# arduino_uno_mod.net
KiCad netlist of a schematic drawn in EAGLE
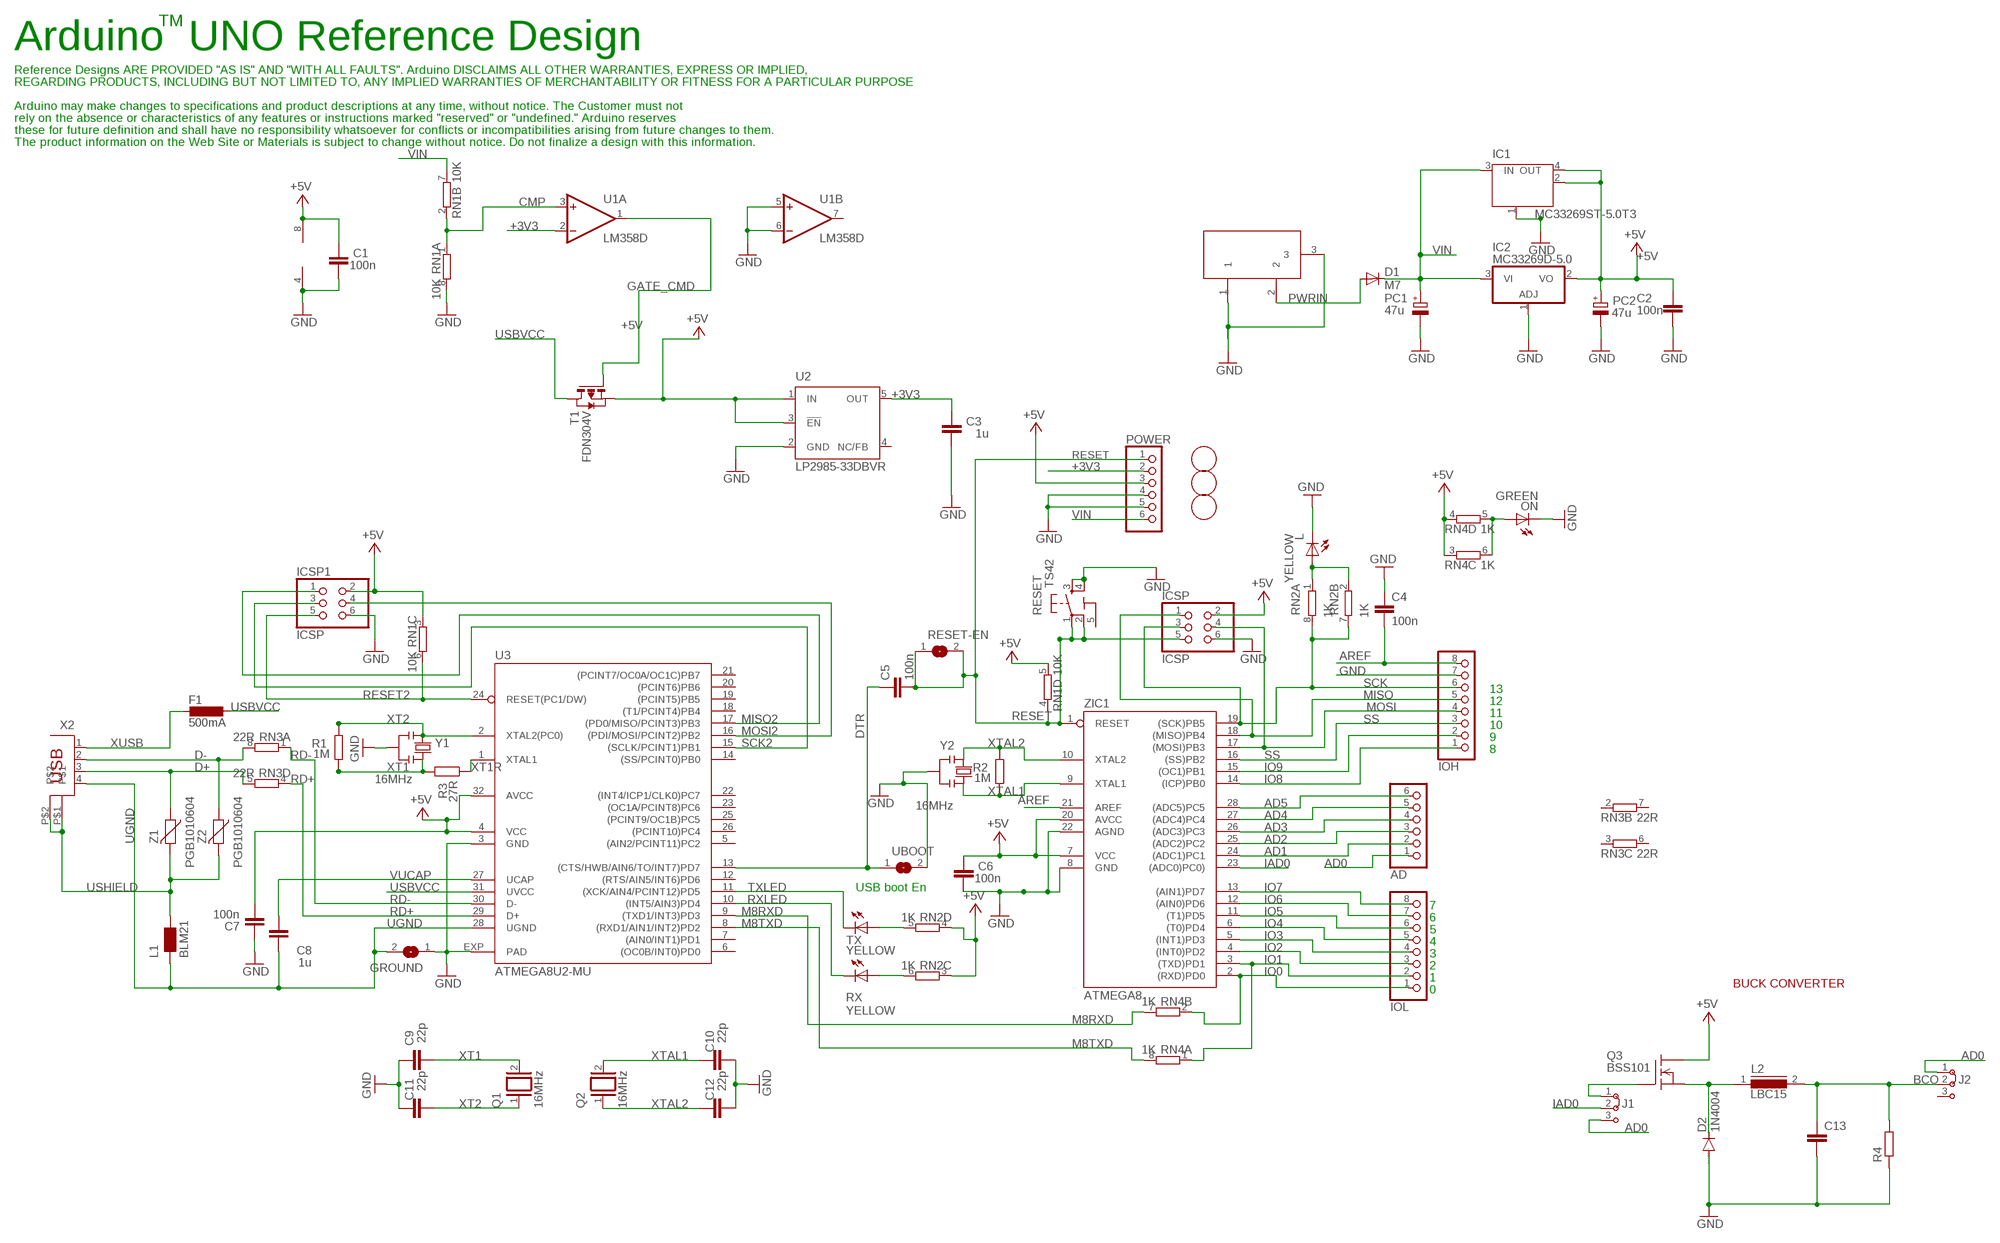
[diagram p0: schematic, sheet 1]

(export (version "E")
  (design (tool "Eeschema 10.0.6"))
  (components
    (comp (ref "AD")
      (value "PINHD-1X6")
      (footprint "eagle-import:1X06")
      (libsource (lib "eagle-import") (part "PINHD-1X6"))
    )
    (comp (ref "C1")
      (value "100n")
      (footprint "eagle-import:C0603-ROUND")
      (libsource (lib "eagle-import") (part "C-EU0603-RND"))
    )
    (comp (ref "C2")
      (value "100n")
      (footprint "eagle-import:C0603-ROUND")
      (libsource (lib "eagle-import") (part "C-EU0603-RND"))
    )
    (comp (ref "C3")
      (value "1u")
      (footprint "eagle-import:C0603-ROUND")
      (libsource (lib "eagle-import") (part "C-EU0603-RND"))
    )
    (comp (ref "C4")
      (value "100n")
      (footprint "eagle-import:C0603-ROUND")
      (libsource (lib "eagle-import") (part "C-EU0603-RND"))
    )
    (comp (ref "C5")
      (value "100n")
      (footprint "eagle-import:C0603-ROUND")
      (libsource (lib "eagle-import") (part "C-EU0603-RND"))
    )
    (comp (ref "C6")
      (value "100n")
      (footprint "eagle-import:C0603-ROUND")
      (libsource (lib "eagle-import") (part "C-EU0603-RND"))
    )
    (comp (ref "C7")
      (value "100n")
      (footprint "eagle-import:C0603-ROUND")
      (libsource (lib "eagle-import") (part "C-EU0603-RND"))
    )
    (comp (ref "C8")
      (value "1u")
      (footprint "eagle-import:C0603-ROUND")
      (libsource (lib "eagle-import") (part "C-EU0603-RND"))
    )
    (comp (ref "C9")
      (value "22p")
      (footprint "eagle-import:C0603-ROUND")
      (libsource (lib "eagle-import") (part "C-EU0603-RND"))
    )
    (comp (ref "C10")
      (value "22p")
      (footprint "eagle-import:C0603-ROUND")
      (libsource (lib "eagle-import") (part "C-EU0603-RND"))
    )
    (comp (ref "C11")
      (value "22p")
      (footprint "eagle-import:C0603-ROUND")
      (libsource (lib "eagle-import") (part "C-EU0603-RND"))
    )
    (comp (ref "C12")
      (value "22p")
      (footprint "eagle-import:C0603-ROUND")
      (libsource (lib "eagle-import") (part "C-EU0603-RND"))
    )
    (comp (ref "C13")
      (value "C2.5/2")
      (footprint "eagle-import:C2.5-2")
      (libsource (lib "eagle-import") (part "C2.5/2"))
    )
    (comp (ref "D1")
      (value "M7")
      (footprint "eagle-import:SMB")
      (libsource (lib "eagle-import") (part "DIODE-SMB"))
    )
    (comp (ref "D2")
      (value "1N4004")
      (footprint "eagle-import:DO41-10")
      (libsource (lib "eagle-import") (part "1N4004"))
    )
    (comp (ref "F1")
      (value "500mA")
      (footprint "eagle-import:L1812")
      (libsource (lib "eagle-import") (part "L-EUL1812"))
    )
    (comp (ref "GROUND")
      (value "SJ")
      (footprint "eagle-import:SJ")
      (libsource (lib "eagle-import") (part "SJ"))
    )
    (comp (ref "IC1")
      (value "MC33269ST-5.0T3")
      (footprint "eagle-import:SOT223")
      (libsource (lib "eagle-import") (part "MC33269ST-3.3T3"))
    )
    (comp (ref "IC2")
      (value "MC33269D-5.0")
      (footprint "eagle-import:DPACK")
      (libsource (lib "eagle-import") (part "MC33269?D-5.0"))
    )
    (comp (ref "ICSP")
      (value "ICSP")
      (footprint "eagle-import:2X03")
      (libsource (lib "eagle-import") (part "PINHD-2X3"))
    )
    (comp (ref "ICSP1")
      (value "ICSP")
      (footprint "eagle-import:2X03")
      (libsource (lib "eagle-import") (part "PINHD-2X3"))
    )
    (comp (ref "IOH")
      (value "PINHD-1X8")
      (footprint "eagle-import:1X08")
      (libsource (lib "eagle-import") (part "PINHD-1X8"))
    )
    (comp (ref "IOL")
      (value "PINHD-1X8")
      (footprint "eagle-import:1X08")
      (libsource (lib "eagle-import") (part "PINHD-1X8"))
    )
    (comp (ref "J1")
      (value "J2X2MM")
      (footprint "eagle-import:04C")
      (libsource (lib "eagle-import") (part "J2X2MM"))
    )
    (comp (ref "J2")
      (value "J2X2MM")
      (footprint "eagle-import:04C")
      (libsource (lib "eagle-import") (part "J2X2MM"))
    )
    (comp (ref "L")
      (value "YELLOW")
      (footprint "eagle-import:CHIP-LED0805")
      (libsource (lib "eagle-import") (part "LEDCHIP-LED0805"))
    )
    (comp (ref "L1")
      (value "BLM21")
      (footprint "eagle-import:0805")
      (libsource (lib "eagle-import") (part "WE-CBF_0805"))
    )
    (comp (ref "L2")
      (value "LBC15")
      (footprint "eagle-import:LBC15")
      (libsource (lib "eagle-import") (part "LBC15"))
    )
    (comp (ref "ON")
      (value "GREEN")
      (footprint "eagle-import:CHIP-LED0805")
      (libsource (lib "eagle-import") (part "LEDCHIP-LED0805"))
    )
    (comp (ref "PC1")
      (value "47u")
      (footprint "eagle-import:PANASONIC_D")
      (libsource (lib "eagle-import") (part "CPOL-EUD"))
    )
    (comp (ref "PC2")
      (value "47u")
      (footprint "eagle-import:PANASONIC_D")
      (libsource (lib "eagle-import") (part "CPOL-EUD"))
    )
    (comp (ref "POWER")
      (value "PINHD-1X6")
      (footprint "eagle-import:1X06")
      (libsource (lib "eagle-import") (part "PINHD-1X6"))
    )
    (comp (ref "Q1")
      (value "16MHz")
      (footprint "eagle-import:QS")
      (libsource (lib "eagle-import") (part "XTAL/S"))
    )
    (comp (ref "Q2")
      (value "16MHz")
      (footprint "eagle-import:QS")
      (libsource (lib "eagle-import") (part "XTAL/S"))
    )
    (comp (ref "Q3")
      (value "BSS101")
      (footprint "eagle-import:TO92")
      (libsource (lib "eagle-import") (part "BSS101"))
    )
    (comp (ref "R1")
      (value "1M")
      (footprint "eagle-import:R0603-ROUND")
      (libsource (lib "eagle-import") (part "R-EU_R0603"))
    )
    (comp (ref "R2")
      (value "1M")
      (footprint "eagle-import:R0603-ROUND")
      (libsource (lib "eagle-import") (part "R-EU_R0603"))
    )
    (comp (ref "R3")
      (value "27R")
      (footprint "eagle-import:R0603-ROUND")
      (libsource (lib "eagle-import") (part "R-EU_R0603"))
    )
    (comp (ref "R4")
      (value "R-EU_0207/10")
      (footprint "eagle-import:0207_10")
      (libsource (lib "eagle-import") (part "rcl_334_R-EU_0207/10"))
    )
    (comp (ref "RESET")
      (value "TS42")
      (footprint "eagle-import:TS42")
      (libsource (lib "eagle-import") (part "TS42"))
    )
    (comp (ref "RESET-EN")
      (value "SJ")
      (footprint "eagle-import:SJ")
      (libsource (lib "eagle-import") (part "SJ"))
    )
    (comp (ref "RN1")
      (value "10K")
      (footprint "eagle-import:CAY16")
      (libsource (lib "eagle-import") (part "4R-NCAY16"))
    )
    (comp (ref "RN2")
      (value "1K")
      (footprint "eagle-import:CAY16")
      (libsource (lib "eagle-import") (part "4R-NCAY16"))
    )
    (comp (ref "RN3")
      (value "22R")
      (footprint "eagle-import:CAY16")
      (libsource (lib "eagle-import") (part "4R-NCAY16"))
    )
    (comp (ref "RN4")
      (value "1K")
      (footprint "eagle-import:CAY16")
      (libsource (lib "eagle-import") (part "4R-NCAY16"))
    )
    (comp (ref "RX")
      (value "YELLOW")
      (footprint "eagle-import:CHIP-LED0805")
      (libsource (lib "eagle-import") (part "LEDCHIP-LED0805"))
    )
    (comp (ref "T1")
      (value "FDN304V")
      (footprint "eagle-import:SOT-23")
      (libsource (lib "eagle-import") (part "PMOSSOT23"))
    )
    (comp (ref "TX")
      (value "YELLOW")
      (footprint "eagle-import:CHIP-LED0805")
      (libsource (lib "eagle-import") (part "LEDCHIP-LED0805"))
    )
    (comp (ref "U$3")
      (value "FIDUCIALMOUNT")
      (footprint "eagle-import:FIDUCIA-MOUNT")
      (libsource (lib "eagle-import") (part "FIDUCIALMOUNT"))
    )
    (comp (ref "U$4")
      (value "FIDUCIALMOUNT")
      (footprint "eagle-import:FIDUCIA-MOUNT")
      (libsource (lib "eagle-import") (part "FIDUCIALMOUNT"))
    )
    (comp (ref "U$6")
      (value "FIDUCIALMOUNT")
      (footprint "eagle-import:FIDUCIA-MOUNT")
      (libsource (lib "eagle-import") (part "FIDUCIALMOUNT"))
    )
    (comp (ref "U1")
      (value "LM358D")
      (footprint "eagle-import:SO08")
      (libsource (lib "eagle-import") (part "LM358D"))
    )
    (comp (ref "U2")
      (value "LP2985-33DBVR")
      (footprint "eagle-import:SOT23-DBV")
      (libsource (lib "eagle-import") (part "TPS77033"))
    )
    (comp (ref "U3")
      (value "ATMEGA8U2-MU")
      (footprint "eagle-import:QFN32")
      (libsource (lib "eagle-import") (part "ATMEGA8U2-MU"))
    )
    (comp (ref "UBOOT")
      (value "SJ")
      (footprint "eagle-import:SJ")
      (libsource (lib "eagle-import") (part "SJ"))
    )
    (comp (ref "X1")
      (value "DC21MMX")
      (footprint "eagle-import:DC-21MM")
      (libsource (lib "eagle-import") (part "DC21MMX"))
    )
    (comp (ref "X2")
      (value "PN61729")
      (footprint "eagle-import:PN61729")
      (libsource (lib "eagle-import") (part "PN61729"))
    )
    (comp (ref "Y1")
      (value "16MHz")
      (footprint "eagle-import:RESONATOR")
      (libsource (lib "eagle-import") (part "RESONATORMU"))
    )
    (comp (ref "Y2")
      (value "16MHz")
      (footprint "eagle-import:RESONATOR")
      (libsource (lib "eagle-import") (part "RESONATORMU"))
    )
    (comp (ref "Z1")
      (value "PGB1010604")
      (footprint "eagle-import:CT_CN0603")
      (libsource (lib "eagle-import") (part "VARISTORCN0603"))
    )
    (comp (ref "Z2")
      (value "PGB1010604")
      (footprint "eagle-import:CT_CN0603")
      (libsource (lib "eagle-import") (part "VARISTORCN0603"))
    )
    (comp (ref "ZIC1")
      (value "ATMEGA8")
      (footprint "eagle-import:DIL28-3")
      (libsource (lib "eagle-import") (part "AT90S4433P"))
    )
  )
  (nets
    (net (code "1") (name "+5V") (class "Default")
      (node (ref "C1") (pin "2") (pinfunction "2_2") (pintype "passive"))
      (node (ref "C2") (pin "2") (pinfunction "2_2") (pintype "passive"))
      (node (ref "C6") (pin "2") (pinfunction "2_2") (pintype "passive"))
      (node (ref "C7") (pin "1") (pinfunction "1_1") (pintype "passive"))
      (node (ref "IC1") (pin "2") (pinfunction "OUT_2") (pintype "passive"))
      (node (ref "IC1") (pin "4") (pinfunction "OUT_4") (pintype "passive"))
      (node (ref "IC2") (pin "2") (pinfunction "VO_2") (pintype "passive"))
      (node (ref "ICSP") (pin "2") (pinfunction "2_2") (pintype "passive"))
      (node (ref "ICSP1") (pin "2") (pinfunction "2_2") (pintype "passive"))
      (node (ref "PC2") (pin "+") (pinfunction "+_+") (pintype "passive"))
      (node (ref "POWER") (pin "3") (pinfunction "3_3") (pintype "passive"))
      (node (ref "Q3") (pin "3") (pinfunction "D_3") (pintype "passive"))
      (node (ref "RN1") (pin "3") (pinfunction "1_3") (pintype "passive"))
      (node (ref "RN1") (pin "5") (pinfunction "2_5") (pintype "passive"))
      (node (ref "RN2") (pin "3") (pinfunction "1_3") (pintype "passive"))
      (node (ref "RN2") (pin "4") (pinfunction "1_4") (pintype "passive"))
      (node (ref "RN4") (pin "3") (pinfunction "1_3") (pintype "passive"))
      (node (ref "RN4") (pin "4") (pinfunction "1_4") (pintype "passive"))
      (node (ref "T1") (pin "2") (pinfunction "S_2") (pintype "passive"))
      (node (ref "U1") (pin "8") (pinfunction "V+_8") (pintype "power_in"))
      (node (ref "U2") (pin "1") (pinfunction "IN_1") (pintype "input"))
      (node (ref "U2") (pin "3") (pinfunction "~{EN}_3") (pintype "input"))
      (node (ref "U3") (pin "32") (pinfunction "AVCC_32") (pintype "power_in"))
      (node (ref "U3") (pin "4") (pinfunction "VCC_4") (pintype "power_in"))
      (node (ref "ZIC1") (pin "20") (pinfunction "AVCC_20") (pintype "power_in"))
      (node (ref "ZIC1") (pin "7") (pinfunction "VCC_7") (pintype "power_in"))
    )
    (net (code "2") (name "/+3V3") (class "Default")
      (node (ref "C3") (pin "2") (pinfunction "2_2") (pintype "passive"))
      (node (ref "POWER") (pin "2") (pinfunction "2_2") (pintype "passive"))
      (node (ref "U1") (pin "2") (pinfunction "-IN_2") (pintype "input"))
      (node (ref "U2") (pin "5") (pinfunction "OUT_5") (pintype "passive"))
    )
    (net (code "3") (name "/5-GND") (class "Default")
      (node (ref "RESET") (pin "5") (pinfunction "5-GND_5") (pintype "power_in"))
    )
    (net (code "4") (name "/AD0") (class "Default")
      (node (ref "AD") (pin "1") (pinfunction "1_1") (pintype "passive"))
      (node (ref "J1") (pin "3") (pinfunction "3_3") (pintype "passive"))
      (node (ref "J2") (pin "1") (pinfunction "1_1") (pintype "passive"))
    )
    (net (code "5") (name "/AD1") (class "Default")
      (node (ref "AD") (pin "2") (pinfunction "2_2") (pintype "passive"))
      (node (ref "ZIC1") (pin "24") (pinfunction "(ADC1)PC1_24") (pintype "bidirectional"))
    )
    (net (code "6") (name "/AD2") (class "Default")
      (node (ref "AD") (pin "3") (pinfunction "3_3") (pintype "passive"))
      (node (ref "ZIC1") (pin "25") (pinfunction "(ADC2)PC2_25") (pintype "bidirectional"))
    )
    (net (code "7") (name "/AD3") (class "Default")
      (node (ref "AD") (pin "4") (pinfunction "4_4") (pintype "passive"))
      (node (ref "ZIC1") (pin "26") (pinfunction "(ADC3)PC3_26") (pintype "bidirectional"))
    )
    (net (code "8") (name "/AD4") (class "Default")
      (node (ref "AD") (pin "5") (pinfunction "5_5") (pintype "passive"))
      (node (ref "ZIC1") (pin "27") (pinfunction "(ADC4)PC4_27") (pintype "bidirectional"))
    )
    (net (code "9") (name "/AD5") (class "Default")
      (node (ref "AD") (pin "6") (pinfunction "6_6") (pintype "passive"))
      (node (ref "ZIC1") (pin "28") (pinfunction "(ADC5)PC5_28") (pintype "bidirectional"))
    )
    (net (code "10") (name "/AREF") (class "Default")
      (node (ref "C4") (pin "2") (pinfunction "2_2") (pintype "passive"))
      (node (ref "IOH") (pin "8") (pinfunction "8_8") (pintype "passive"))
      (node (ref "ZIC1") (pin "21") (pinfunction "AREF_21") (pintype "passive"))
    )
    (net (code "11") (name "/BCO") (class "Default")
      (node (ref "C13") (pin "1") (pinfunction "1_1") (pintype "passive"))
      (node (ref "J2") (pin "2") (pinfunction "2_2") (pintype "passive"))
      (node (ref "L2") (pin "2") (pinfunction "2_2") (pintype "passive"))
      (node (ref "R4") (pin "2") (pinfunction "2_2") (pintype "passive"))
    )
    (net (code "12") (name "/CMP") (class "Default")
      (node (ref "RN1") (pin "1") (pinfunction "1_1") (pintype "passive"))
      (node (ref "RN1") (pin "2") (pinfunction "1_2") (pintype "passive"))
      (node (ref "U1") (pin "3") (pinfunction "+IN_3") (pintype "input"))
    )
    (net (code "13") (name "/D+") (class "Default")
      (node (ref "RN3") (pin "5") (pinfunction "2_5") (pintype "passive"))
      (node (ref "X2") (pin "3") (pinfunction "3_3") (pintype "bidirectional"))
      (node (ref "Z1") (pin "1") (pinfunction "1_1") (pintype "passive"))
    )
    (net (code "14") (name "/D-") (class "Default")
      (node (ref "RN3") (pin "8") (pinfunction "2_8") (pintype "passive"))
      (node (ref "X2") (pin "2") (pinfunction "2_2") (pintype "bidirectional"))
      (node (ref "Z2") (pin "1") (pinfunction "1_1") (pintype "passive"))
    )
    (net (code "15") (name "/DTR") (class "Default")
      (node (ref "C5") (pin "1") (pinfunction "1_1") (pintype "passive"))
      (node (ref "U3") (pin "13") (pinfunction "(CTS/HWB/AIN6/TO/INT7)PD7_13") (pintype "bidirectional"))
      (node (ref "UBOOT") (pin "1") (pinfunction "1_1") (pintype "passive"))
    )
    (net (code "16") (name "/GATE_CMD") (class "Default")
      (node (ref "T1") (pin "3") (pinfunction "G_3") (pintype "passive"))
      (node (ref "U1") (pin "1") (pinfunction "OUT_1") (pintype "output"))
    )
    (net (code "17") (name "/IAD0") (class "Default")
      (node (ref "J1") (pin "2") (pinfunction "2_2") (pintype "passive"))
      (node (ref "ZIC1") (pin "23") (pinfunction "(ADC0)PC0)_23") (pintype "bidirectional"))
    )
    (net (code "18") (name "/IO0") (class "Default")
      (node (ref "IOL") (pin "1") (pinfunction "1_1") (pintype "passive"))
      (node (ref "RN4") (pin "2") (pinfunction "1_2") (pintype "passive"))
      (node (ref "ZIC1") (pin "2") (pinfunction "(RXD)PD0_2") (pintype "bidirectional"))
    )
    (net (code "19") (name "/IO1") (class "Default")
      (node (ref "IOL") (pin "2") (pinfunction "2_2") (pintype "passive"))
      (node (ref "RN4") (pin "1") (pinfunction "1_1") (pintype "passive"))
      (node (ref "ZIC1") (pin "3") (pinfunction "(TXD)PD1_3") (pintype "bidirectional"))
    )
    (net (code "20") (name "/IO2") (class "Default")
      (node (ref "IOL") (pin "3") (pinfunction "3_3") (pintype "passive"))
      (node (ref "ZIC1") (pin "4") (pinfunction "(INT0)PD2_4") (pintype "bidirectional"))
    )
    (net (code "21") (name "/IO3") (class "Default")
      (node (ref "IOL") (pin "4") (pinfunction "4_4") (pintype "passive"))
      (node (ref "ZIC1") (pin "5") (pinfunction "(INT1)PD3_5") (pintype "bidirectional"))
    )
    (net (code "22") (name "/IO4") (class "Default")
      (node (ref "IOL") (pin "5") (pinfunction "5_5") (pintype "passive"))
      (node (ref "ZIC1") (pin "6") (pinfunction "(T0)PD4_6") (pintype "bidirectional"))
    )
    (net (code "23") (name "/IO5") (class "Default")
      (node (ref "IOL") (pin "6") (pinfunction "6_6") (pintype "passive"))
      (node (ref "ZIC1") (pin "11") (pinfunction "(T1)PD5_11") (pintype "bidirectional"))
    )
    (net (code "24") (name "/IO6") (class "Default")
      (node (ref "IOL") (pin "7") (pinfunction "7_7") (pintype "passive"))
      (node (ref "ZIC1") (pin "12") (pinfunction "(AIN0)PD6_12") (pintype "bidirectional"))
    )
    (net (code "25") (name "/IO7") (class "Default")
      (node (ref "IOL") (pin "8") (pinfunction "8_8") (pintype "passive"))
      (node (ref "ZIC1") (pin "13") (pinfunction "(AIN1)PD7_13") (pintype "bidirectional"))
    )
    (net (code "26") (name "/IO8") (class "Default")
      (node (ref "IOH") (pin "1") (pinfunction "1_1") (pintype "passive"))
      (node (ref "ZIC1") (pin "14") (pinfunction "(ICP)PB0_14") (pintype "bidirectional"))
    )
    (net (code "27") (name "/IO9") (class "Default")
      (node (ref "IOH") (pin "2") (pinfunction "2_2") (pintype "passive"))
      (node (ref "ZIC1") (pin "15") (pinfunction "(OC1)PB1_15") (pintype "bidirectional"))
    )
    (net (code "28") (name "/M8RXD") (class "Default")
      (node (ref "RN4") (pin "7") (pinfunction "2_7") (pintype "passive"))
      (node (ref "U3") (pin "9") (pinfunction "(TXD1/INT3)PD3_9") (pintype "bidirectional"))
    )
    (net (code "29") (name "/M8TXD") (class "Default")
      (node (ref "RN4") (pin "8") (pinfunction "2_8") (pintype "passive"))
      (node (ref "U3") (pin "8") (pinfunction "(RXD1/AIN1/INT2)PD2_8") (pintype "bidirectional"))
    )
    (net (code "30") (name "/MISO") (class "Default")
      (node (ref "ICSP") (pin "1") (pinfunction "1_1") (pintype "passive"))
      (node (ref "IOH") (pin "5") (pinfunction "5_5") (pintype "passive"))
      (node (ref "ZIC1") (pin "18") (pinfunction "(MISO)PB4_18") (pintype "bidirectional"))
    )
    (net (code "31") (name "/MISO2") (class "Default")
      (node (ref "ICSP1") (pin "1") (pinfunction "1_1") (pintype "passive"))
      (node (ref "U3") (pin "17") (pinfunction "(PD0/MISO/PCINT3)PB3_17") (pintype "bidirectional"))
    )
    (net (code "32") (name "/MOSI") (class "Default")
      (node (ref "ICSP") (pin "4") (pinfunction "4_4") (pintype "passive"))
      (node (ref "IOH") (pin "4") (pinfunction "4_4") (pintype "passive"))
      (node (ref "ZIC1") (pin "17") (pinfunction "(MOSI)PB3_17") (pintype "bidirectional"))
    )
    (net (code "33") (name "/MOSI2") (class "Default")
      (node (ref "ICSP1") (pin "4") (pinfunction "4_4") (pintype "passive"))
      (node (ref "U3") (pin "16") (pinfunction "(PDI/MOSI/PCINT2)PB2_16") (pintype "bidirectional"))
    )
    (net (code "34") (name "/PWRIN") (class "Default")
      (node (ref "D1") (pin "A") (pinfunction "A_A") (pintype "passive"))
      (node (ref "X1") (pin "2") (pinfunction "2_2") (pintype "power_in"))
    )
    (net (code "35") (name "/RD+") (class "Default")
      (node (ref "RN3") (pin "4") (pinfunction "1_4") (pintype "passive"))
      (node (ref "U3") (pin "29") (pinfunction "D+_29") (pintype "bidirectional"))
    )
    (net (code "36") (name "/RD-") (class "Default")
      (node (ref "RN3") (pin "1") (pinfunction "1_1") (pintype "passive"))
      (node (ref "U3") (pin "30") (pinfunction "D-_30") (pintype "bidirectional"))
    )
    (net (code "37") (name "/RESET") (class "Default")
      (node (ref "C5") (pin "2") (pinfunction "2_2") (pintype "passive"))
      (node (ref "ICSP") (pin "5") (pinfunction "5_5") (pintype "passive"))
      (node (ref "POWER") (pin "1") (pinfunction "1_1") (pintype "passive"))
      (node (ref "RESET") (pin "1") (pinfunction "1_1") (pintype "passive"))
      (node (ref "RESET") (pin "2") (pinfunction "2_2") (pintype "passive"))
      (node (ref "RESET-EN") (pin "1") (pinfunction "1_1") (pintype "passive"))
      (node (ref "RESET-EN") (pin "2") (pinfunction "2_2") (pintype "passive"))
      (node (ref "RN1") (pin "4") (pinfunction "1_4") (pintype "passive"))
      (node (ref "ZIC1") (pin "1") (pinfunction "RESET_1") (pintype "input"))
    )
    (net (code "38") (name "/RESET2") (class "Default")
      (node (ref "ICSP1") (pin "5") (pinfunction "5_5") (pintype "passive"))
      (node (ref "RN1") (pin "6") (pinfunction "2_6") (pintype "passive"))
      (node (ref "U3") (pin "24") (pinfunction "RESET(PC1/DW)_24") (pintype "input"))
    )
    (net (code "39") (name "/RXLED") (class "Default")
      (node (ref "RX") (pin "C") (pinfunction "C_C") (pintype "passive"))
      (node (ref "U3") (pin "10") (pinfunction "(INT5/AIN3)PD4_10") (pintype "bidirectional"))
    )
    (net (code "40") (name "/SCK") (class "Default")
      (node (ref "ICSP") (pin "3") (pinfunction "3_3") (pintype "passive"))
      (node (ref "IOH") (pin "6") (pinfunction "6_6") (pintype "passive"))
      (node (ref "RN2") (pin "7") (pinfunction "2_7") (pintype "passive"))
      (node (ref "RN2") (pin "8") (pinfunction "2_8") (pintype "passive"))
      (node (ref "ZIC1") (pin "19") (pinfunction "(SCK)PB5_19") (pintype "bidirectional"))
    )
    (net (code "41") (name "/SCK2") (class "Default")
      (node (ref "ICSP1") (pin "3") (pinfunction "3_3") (pintype "passive"))
      (node (ref "U3") (pin "15") (pinfunction "(SCLK/PCINT1)PB1_15") (pintype "bidirectional"))
    )
    (net (code "42") (name "/SS") (class "Default")
      (node (ref "IOH") (pin "3") (pinfunction "3_3") (pintype "passive"))
      (node (ref "ZIC1") (pin "16") (pinfunction "(SS)PB2_16") (pintype "bidirectional"))
    )
    (net (code "43") (name "/TXLED") (class "Default")
      (node (ref "TX") (pin "C") (pinfunction "C_C") (pintype "passive"))
      (node (ref "U3") (pin "11") (pinfunction "(XCK/AIN4/PCINT12)PD5_11") (pintype "bidirectional"))
    )
    (net (code "44") (name "/UGND") (class "Default")
      (node (ref "C8") (pin "2") (pinfunction "2_2") (pintype "passive"))
      (node (ref "GROUND") (pin "2") (pinfunction "2_2") (pintype "passive"))
      (node (ref "L1") (pin "1") (pinfunction "1_1") (pintype "passive"))
      (node (ref "U3") (pin "28") (pinfunction "UGND_28") (pintype "power_in"))
      (node (ref "X2") (pin "4") (pinfunction "4_4") (pintype "bidirectional"))
    )
    (net (code "45") (name "/USBVCC") (class "Default")
      (node (ref "F1") (pin "1") (pinfunction "1_1") (pintype "passive"))
      (node (ref "T1") (pin "1") (pinfunction "D_1") (pintype "passive"))
      (node (ref "U3") (pin "31") (pinfunction "UVCC_31") (pintype "power_in"))
    )
    (net (code "46") (name "/USHIELD") (class "Default")
      (node (ref "L1") (pin "2") (pinfunction "2_2") (pintype "passive"))
      (node (ref "X2") (pin "P$1") (pinfunction "P$1_P$1") (pintype "bidirectional"))
      (node (ref "X2") (pin "P$2") (pinfunction "P$2_P$2") (pintype "bidirectional"))
      (node (ref "Z1") (pin "2") (pinfunction "2_2") (pintype "passive"))
      (node (ref "Z2") (pin "2") (pinfunction "2_2") (pintype "passive"))
    )
    (net (code "47") (name "/VIN") (class "Default")
      (node (ref "D1") (pin "C") (pinfunction "C_C") (pintype "passive"))
      (node (ref "IC1") (pin "3") (pinfunction "IN_3") (pintype "input"))
      (node (ref "IC2") (pin "3") (pinfunction "VI_3") (pintype "input"))
      (node (ref "PC1") (pin "+") (pinfunction "+_+") (pintype "passive"))
      (node (ref "POWER") (pin "6") (pinfunction "6_6") (pintype "passive"))
      (node (ref "RN1") (pin "7") (pinfunction "2_7") (pintype "passive"))
    )
    (net (code "48") (name "/VUCAP") (class "Default")
      (node (ref "C8") (pin "1") (pinfunction "1_1") (pintype "passive"))
      (node (ref "U3") (pin "27") (pinfunction "UCAP_27") (pintype "passive"))
    )
    (net (code "49") (name "/XT1") (class "Default")
      (node (ref "C9") (pin "1") (pinfunction "1_1") (pintype "passive"))
      (node (ref "Q1") (pin "2") (pinfunction "2_2") (pintype "passive"))
      (node (ref "R1") (pin "1") (pinfunction "1_1") (pintype "passive"))
      (node (ref "R3") (pin "2") (pinfunction "2_2") (pintype "passive"))
      (node (ref "Y1") (pin "3") (pinfunction "3_3") (pintype "passive"))
    )
    (net (code "50") (name "/XT1R") (class "Default")
      (node (ref "R3") (pin "1") (pinfunction "1_1") (pintype "passive"))
      (node (ref "U3") (pin "1") (pinfunction "XTAL1_1") (pintype "bidirectional"))
    )
    (net (code "51") (name "/XT2") (class "Default")
      (node (ref "C11") (pin "1") (pinfunction "1_1") (pintype "passive"))
      (node (ref "Q1") (pin "1") (pinfunction "1_1") (pintype "passive"))
      (node (ref "R1") (pin "2") (pinfunction "2_2") (pintype "passive"))
      (node (ref "U3") (pin "2") (pinfunction "XTAL2(PC0)_2") (pintype "bidirectional"))
      (node (ref "Y1") (pin "1") (pinfunction "1_1") (pintype "passive"))
    )
    (net (code "52") (name "/XTAL1") (class "Default")
      (node (ref "C10") (pin "2") (pinfunction "2_2") (pintype "passive"))
      (node (ref "Q2") (pin "2") (pinfunction "2_2") (pintype "passive"))
      (node (ref "R2") (pin "1") (pinfunction "1_1") (pintype "passive"))
      (node (ref "Y2") (pin "3") (pinfunction "3_3") (pintype "passive"))
      (node (ref "ZIC1") (pin "9") (pinfunction "XTAL1_9") (pintype "bidirectional"))
    )
    (net (code "53") (name "/XTAL2") (class "Default")
      (node (ref "C12") (pin "2") (pinfunction "2_2") (pintype "passive"))
      (node (ref "Q2") (pin "1") (pinfunction "1_1") (pintype "passive"))
      (node (ref "R2") (pin "2") (pinfunction "2_2") (pintype "passive"))
      (node (ref "Y2") (pin "1") (pinfunction "1_1") (pintype "passive"))
      (node (ref "ZIC1") (pin "10") (pinfunction "XTAL2_10") (pintype "bidirectional"))
    )
    (net (code "54") (name "/XUSB") (class "Default")
      (node (ref "F1") (pin "2") (pinfunction "2_2") (pintype "passive"))
      (node (ref "X2") (pin "1") (pinfunction "1_1") (pintype "bidirectional"))
    )
    (net (code "55") (name "GND") (class "Default")
      (node (ref "C1") (pin "1") (pinfunction "1_1") (pintype "passive"))
      (node (ref "C10") (pin "1") (pinfunction "1_1") (pintype "passive"))
      (node (ref "C11") (pin "2") (pinfunction "2_2") (pintype "passive"))
      (node (ref "C12") (pin "1") (pinfunction "1_1") (pintype "passive"))
      (node (ref "C13") (pin "2") (pinfunction "2_2") (pintype "passive"))
      (node (ref "C2") (pin "1") (pinfunction "1_1") (pintype "passive"))
      (node (ref "C3") (pin "1") (pinfunction "1_1") (pintype "passive"))
      (node (ref "C4") (pin "1") (pinfunction "1_1") (pintype "passive"))
      (node (ref "C6") (pin "1") (pinfunction "1_1") (pintype "passive"))
      (node (ref "C7") (pin "2") (pinfunction "2_2") (pintype "passive"))
      (node (ref "C9") (pin "2") (pinfunction "2_2") (pintype "passive"))
      (node (ref "D2") (pin "A") (pinfunction "A_A") (pintype "passive"))
      (node (ref "GROUND") (pin "1") (pinfunction "1_1") (pintype "passive"))
      (node (ref "IC1") (pin "1") (pinfunction "GND/ADJ_1") (pintype "input"))
      (node (ref "IC2") (pin "1") (pinfunction "ADJ_1") (pintype "input"))
      (node (ref "ICSP") (pin "6") (pinfunction "6_6") (pintype "passive"))
      (node (ref "ICSP1") (pin "6") (pinfunction "6_6") (pintype "passive"))
      (node (ref "IOH") (pin "7") (pinfunction "7_7") (pintype "passive"))
      (node (ref "L") (pin "C") (pinfunction "C_C") (pintype "passive"))
      (node (ref "ON") (pin "C") (pinfunction "C_C") (pintype "passive"))
      (node (ref "PC1") (pin "-") (pinfunction "-_-") (pintype "passive"))
      (node (ref "PC2") (pin "-") (pinfunction "-_-") (pintype "passive"))
      (node (ref "POWER") (pin "4") (pinfunction "4_4") (pintype "passive"))
      (node (ref "POWER") (pin "5") (pinfunction "5_5") (pintype "passive"))
      (node (ref "R4") (pin "1") (pinfunction "1_1") (pintype "passive"))
      (node (ref "RESET") (pin "3") (pinfunction "3_3") (pintype "passive"))
      (node (ref "RESET") (pin "4") (pinfunction "4_4") (pintype "passive"))
      (node (ref "RN1") (pin "8") (pinfunction "2_8") (pintype "passive"))
      (node (ref "U1") (pin "4") (pinfunction "V-_4") (pintype "power_in"))
      (node (ref "U1") (pin "5") (pinfunction "+IN_5") (pintype "input"))
      (node (ref "U1") (pin "6") (pinfunction "-IN_6") (pintype "input"))
      (node (ref "U2") (pin "2") (pinfunction "GND_2") (pintype "power_in"))
      (node (ref "U3") (pin "3") (pinfunction "GND_3") (pintype "power_in"))
      (node (ref "U3") (pin "EXP") (pinfunction "PAD_EXP") (pintype "power_in"))
      (node (ref "UBOOT") (pin "2") (pinfunction "2_2") (pintype "passive"))
      (node (ref "X1") (pin "1") (pinfunction "1_1") (pintype "power_in"))
      (node (ref "X1") (pin "3") (pinfunction "3_3") (pintype "power_in"))
      (node (ref "Y1") (pin "2") (pinfunction "2_2") (pintype "passive"))
      (node (ref "Y2") (pin "2") (pinfunction "2_2") (pintype "passive"))
      (node (ref "ZIC1") (pin "22") (pinfunction "AGND_22") (pintype "power_in"))
      (node (ref "ZIC1") (pin "8") (pinfunction "GND_8") (pintype "power_in"))
    )
    (net (code "56") (name "Net-(Q3-G)") (class "Default")
      (node (ref "J1") (pin "1") (pinfunction "1_1") (pintype "passive"))
      (node (ref "Q3") (pin "2") (pinfunction "G_2") (pintype "passive"))
    )
    (net (code "57") (name "Net-(Q3-S)") (class "Default")
      (node (ref "D2") (pin "C") (pinfunction "C_C") (pintype "passive"))
      (node (ref "L2") (pin "1") (pinfunction "1_1") (pintype "passive"))
      (node (ref "Q3") (pin "1") (pinfunction "S_1") (pintype "passive"))
    )
    (net (code "58") (name "Net-(RN2B-1)") (class "Default")
      (node (ref "L") (pin "A") (pinfunction "A_A") (pintype "passive"))
      (node (ref "RN2") (pin "1") (pinfunction "1_1") (pintype "passive"))
      (node (ref "RN2") (pin "2") (pinfunction "1_2") (pintype "passive"))
    )
    (net (code "59") (name "Net-(RN2C-2)") (class "Default")
      (node (ref "RN2") (pin "6") (pinfunction "2_6") (pintype "passive"))
      (node (ref "RX") (pin "A") (pinfunction "A_A") (pintype "passive"))
    )
    (net (code "60") (name "Net-(RN2D-2)") (class "Default")
      (node (ref "RN2") (pin "5") (pinfunction "2_5") (pintype "passive"))
      (node (ref "TX") (pin "A") (pinfunction "A_A") (pintype "passive"))
    )
    (net (code "61") (name "Net-(RN4C-2)") (class "Default")
      (node (ref "ON") (pin "A") (pinfunction "A_A") (pintype "passive"))
      (node (ref "RN4") (pin "5") (pinfunction "2_5") (pintype "passive"))
      (node (ref "RN4") (pin "6") (pinfunction "2_6") (pintype "passive"))
    )
    (net (code "62") (name "unconnected-(J2-Pad3)") (class "Default")
      (node (ref "J2") (pin "3") (pinfunction "3_3") (pintype "passive"))
    )
    (net (code "63") (name "unconnected-(RN3B-1-Pad2)") (class "Default")
      (node (ref "RN3") (pin "2") (pinfunction "1_2") (pintype "passive"))
    )
    (net (code "64") (name "unconnected-(RN3B-2-Pad7)") (class "Default")
      (node (ref "RN3") (pin "7") (pinfunction "2_7") (pintype "passive"))
    )
    (net (code "65") (name "unconnected-(RN3C-1-Pad3)") (class "Default")
      (node (ref "RN3") (pin "3") (pinfunction "1_3") (pintype "passive"))
    )
    (net (code "66") (name "unconnected-(RN3C-2-Pad6)") (class "Default")
      (node (ref "RN3") (pin "6") (pinfunction "2_6") (pintype "passive"))
    )
    (net (code "67") (name "unconnected-(U1B-OUT-Pad7)") (class "Default")
      (node (ref "U1") (pin "7") (pinfunction "OUT_7") (pintype "output"))
    )
    (net (code "68") (name "unconnected-(U2-NC{slash}FB-Pad4)") (class "Default")
      (node (ref "U2") (pin "4") (pinfunction "NC/FB_4") (pintype "passive"))
    )
    (net (code "69") (name "unconnected-(U3-(AIN0{slash}INT1)PD1-Pad7)") (class "Default")
      (node (ref "U3") (pin "7") (pinfunction "(AIN0/INT1)PD1_7") (pintype "bidirectional"))
    )
    (net (code "70") (name "unconnected-(U3-(AIN2{slash}PCINT11)PC2-Pad5)") (class "Default")
      (node (ref "U3") (pin "5") (pinfunction "(AIN2/PCINT11)PC2_5") (pintype "bidirectional"))
    )
    (net (code "71") (name "unconnected-(U3-(INT4{slash}ICP1{slash}CLK0)PC7-Pad22)") (class "Default")
      (node (ref "U3") (pin "22") (pinfunction "(INT4/ICP1/CLK0)PC7_22") (pintype "bidirectional"))
    )
    (net (code "72") (name "unconnected-(U3-(OC0B{slash}INT0)PD0-Pad6)") (class "Default")
      (node (ref "U3") (pin "6") (pinfunction "(OC0B/INT0)PD0_6") (pintype "bidirectional"))
    )
    (net (code "73") (name "unconnected-(U3-(OC1A{slash}PCINT8)PC6-Pad23)") (class "Default")
      (node (ref "U3") (pin "23") (pinfunction "(OC1A/PCINT8)PC6_23") (pintype "bidirectional"))
    )
    (net (code "74") (name "unconnected-(U3-(PCINT5)PB5-Pad19)") (class "Default")
      (node (ref "U3") (pin "19") (pinfunction "(PCINT5)PB5_19") (pintype "bidirectional"))
    )
    (net (code "75") (name "unconnected-(U3-(PCINT6)PB6-Pad20)") (class "Default")
      (node (ref "U3") (pin "20") (pinfunction "(PCINT6)PB6_20") (pintype "bidirectional"))
    )
    (net (code "76") (name "unconnected-(U3-(PCINT7{slash}OC0A{slash}OC1C)PB7-Pad21)") (class "Default")
      (node (ref "U3") (pin "21") (pinfunction "(PCINT7/OC0A/OC1C)PB7_21") (pintype "bidirectional"))
    )
    (net (code "77") (name "unconnected-(U3-(PCINT9{slash}OC1B)PC5-Pad25)") (class "Default")
      (node (ref "U3") (pin "25") (pinfunction "(PCINT9/OC1B)PC5_25") (pintype "bidirectional"))
    )
    (net (code "78") (name "unconnected-(U3-(PCINT10)PC4-Pad26)") (class "Default")
      (node (ref "U3") (pin "26") (pinfunction "(PCINT10)PC4_26") (pintype "bidirectional"))
    )
    (net (code "79") (name "unconnected-(U3-(RTS{slash}AIN5{slash}INT6)PD6-Pad12)") (class "Default")
      (node (ref "U3") (pin "12") (pinfunction "(RTS/AIN5/INT6)PD6_12") (pintype "bidirectional"))
    )
    (net (code "80") (name "unconnected-(U3-(SS{slash}PCINT0)PB0-Pad14)") (class "Default")
      (node (ref "U3") (pin "14") (pinfunction "(SS/PCINT0)PB0_14") (pintype "bidirectional"))
    )
    (net (code "81") (name "unconnected-(U3-(T1{slash}PCINT4)PB4-Pad18)") (class "Default")
      (node (ref "U3") (pin "18") (pinfunction "(T1/PCINT4)PB4_18") (pintype "bidirectional"))
    )
  )
)
